# TempEnhanced.net
KiCad netlist of a schematic drawn in Altium Designer
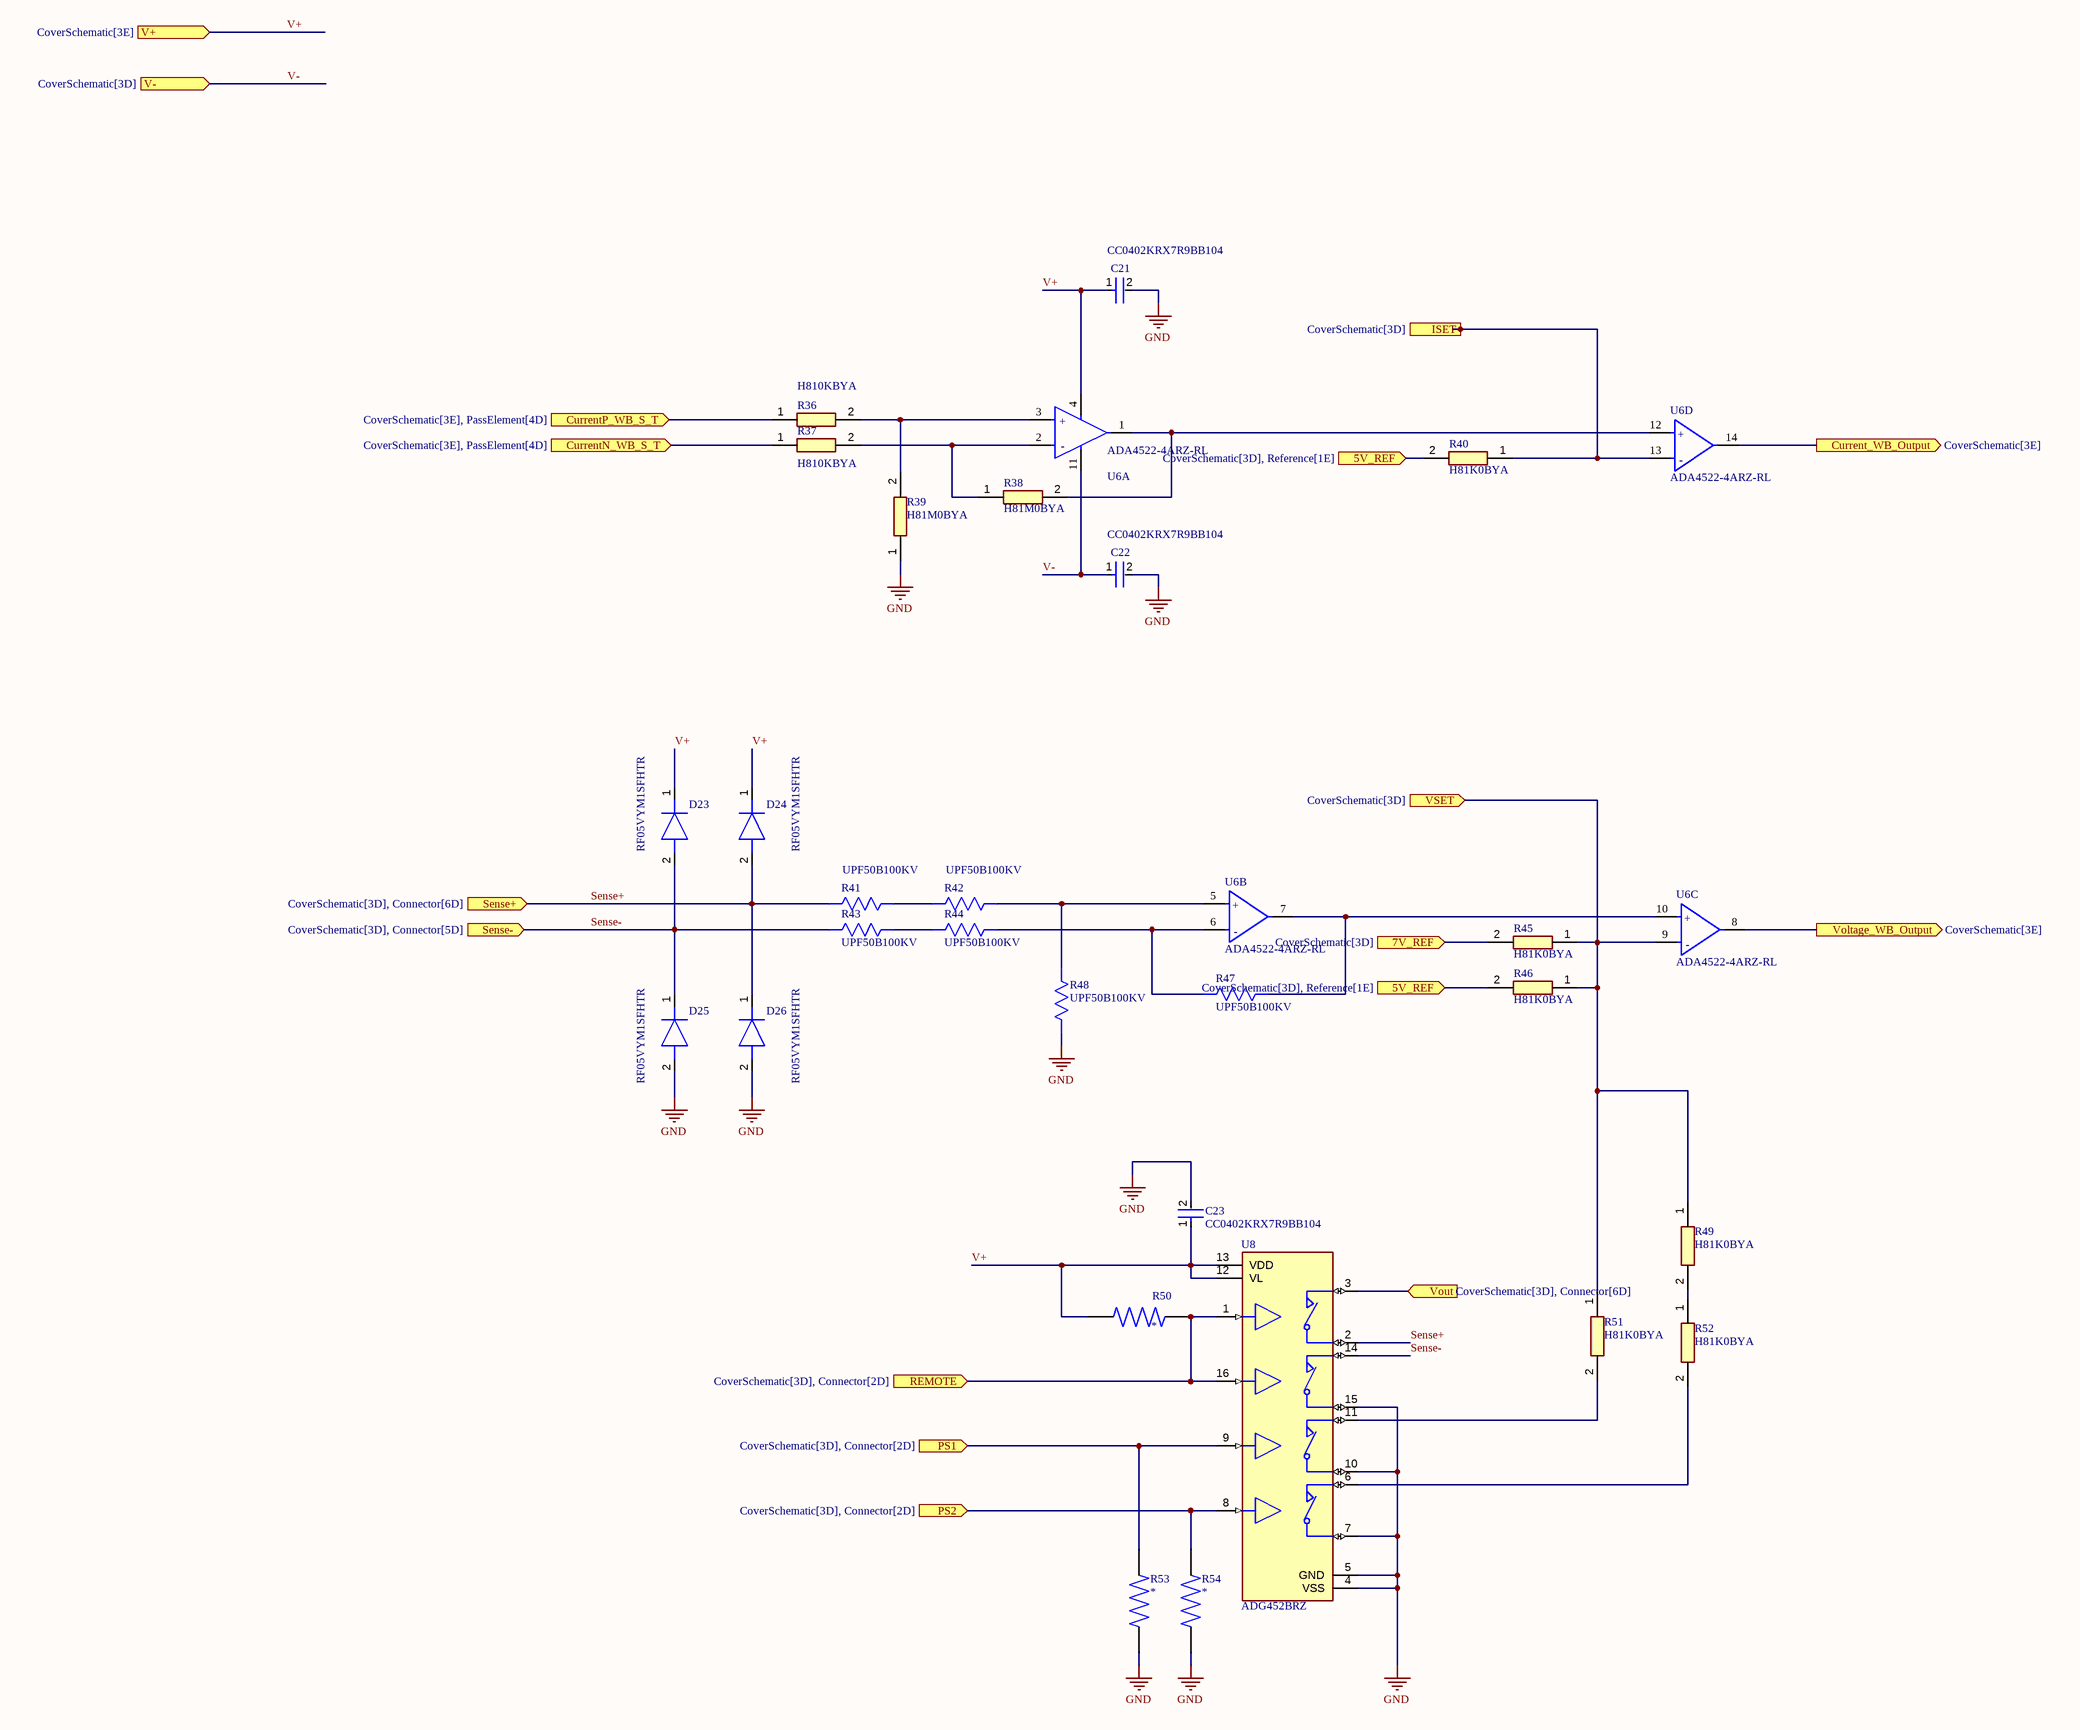
[diagram p0: TempEnhanced.SchDoc]

(export (version "E")
  (design (tool "Eeschema 10.0.6"))
  (components
    (comp (ref "C21")
      (value "CC0402KRX7R9BB104")
      (footprint "FP-CC0402-MFG")
      (description "CAP CER 0.1UF 50V X7R 0402")
      (fields
        (field (name "MANUFACTURER") "YAGEO")
        (field (name "OCTOPART") "https://octopart.com/cc0402krx7r9bb104-yageo-56536067")
      )
      (libsource (lib "Altium Content Vault") (part "11868f565c42a9108669ba33697ecf6"))
    )
    (comp (ref "C22")
      (value "CC0402KRX7R9BB104")
      (footprint "FP-CC0402-MFG")
      (description "CAP CER 0.1UF 50V X7R 0402")
      (fields
        (field (name "MANUFACTURER") "YAGEO")
        (field (name "OCTOPART") "https://octopart.com/cc0402krx7r9bb104-yageo-56536067")
      )
      (libsource (lib "Altium Content Vault") (part "11868f565c42a9108669ba33697ecf6"))
    )
    (comp (ref "C23")
      (value "CC0402KRX7R9BB104")
      (footprint "FP-CC0402-MFG")
      (description "CAP CER 0.1UF 50V X7R 0402")
      (fields
        (field (name "MANUFACTURER") "YAGEO")
        (field (name "OCTOPART") "https://octopart.com/cc0402krx7r9bb104-yageo-56536067")
      )
      (libsource (lib "Altium Content Vault") (part "11868f565c42a9108669ba33697ecf6"))
    )
    (comp (ref "D23")
      (value "RF05VYM1SFHTR")
      (footprint "SamacSys:RF05VYM1SFHTR")
      (description "Diode")
      (fields (field (name "MOUSER PART NUMBER") "755-RF05VYM1SFHTR"))
      (libsource (lib "*") (part "RF05VYM1SFHTR"))
    )
    (comp (ref "D24")
      (value "RF05VYM1SFHTR")
      (footprint "SamacSys:RF05VYM1SFHTR")
      (description "Diode")
      (fields (field (name "MOUSER PART NUMBER") "755-RF05VYM1SFHTR"))
      (libsource (lib "*") (part "RF05VYM1SFHTR"))
    )
    (comp (ref "D25")
      (value "RF05VYM1SFHTR")
      (footprint "SamacSys:RF05VYM1SFHTR")
      (description "Diode")
      (fields (field (name "MOUSER PART NUMBER") "755-RF05VYM1SFHTR"))
      (libsource (lib "*") (part "RF05VYM1SFHTR"))
    )
    (comp (ref "D26")
      (value "RF05VYM1SFHTR")
      (footprint "SamacSys:RF05VYM1SFHTR")
      (description "Diode")
      (fields (field (name "MOUSER PART NUMBER") "755-RF05VYM1SFHTR"))
      (libsource (lib "*") (part "RF05VYM1SFHTR"))
    )
    (comp (ref "R36")
      (value "H810KBYA")
      (footprint "SamacSys:RESAD1690W60L710D245")
      (description "Resistor")
      (fields (field (name "MOUSER PART NUMBER") "279-H810KBYA"))
      (libsource (lib "") (part "H810KBYA_2"))
    )
    (comp (ref "R37")
      (value "H810KBYA")
      (footprint "SamacSys:RESAD1690W60L710D245")
      (description "Resistor")
      (fields (field (name "MOUSER PART NUMBER") "279-H810KBYA"))
      (libsource (lib "") (part "H810KBYA_2"))
    )
    (comp (ref "R38")
      (value "H81M0BYA")
      (footprint "SamacSys:RESAD1690W60L710D245")
      (description "Resistor")
      (fields
        (field (name "MANUFACTURER_PART_NUMBER") "H810KBYA")
        (field (name "MOUSER PART NUMBER") "279-H810KBYA")
      )
      (libsource (lib "") (part "H810KBYA_2"))
    )
    (comp (ref "R39")
      (value "H81M0BYA")
      (footprint "SamacSys:RESAD1690W60L710D245")
      (description "Resistor")
      (fields
        (field (name "MANUFACTURER_PART_NUMBER") "H810KBYA")
        (field (name "MOUSER PART NUMBER") "279-H810KBYA")
      )
      (libsource (lib "") (part "H810KBYA_3"))
    )
    (comp (ref "R40")
      (value "H81K0BYA")
      (footprint "SamacSys:RESAD1690W60L710D245")
      (description "Resistor")
      (fields
        (field (name "MANUFACTURER_PART_NUMBER") "H810KBYA")
        (field (name "MOUSER PART NUMBER") "279-H810KBYA")
      )
      (libsource (lib "") (part "H810KBYA_1"))
    )
    (comp (ref "R41")
      (value "UPF50B100KV")
      (footprint "RES_UPF50B2K0V_TEC")
      (description "No Description Available")
      (libsource (lib "UPF50B100RV") (part "UPF50B100RV"))
    )
    (comp (ref "R42")
      (value "UPF50B100KV")
      (footprint "RES_UPF50B2K0V_TEC")
      (description "No Description Available")
      (libsource (lib "UPF50B100RV") (part "UPF50B100RV"))
    )
    (comp (ref "R43")
      (value "UPF50B100KV")
      (footprint "RES_UPF50B2K0V_TEC")
      (description "No Description Available")
      (libsource (lib "UPF50B100RV") (part "UPF50B100RV"))
    )
    (comp (ref "R44")
      (value "UPF50B100KV")
      (footprint "RES_UPF50B2K0V_TEC")
      (description "No Description Available")
      (libsource (lib "UPF50B100RV") (part "UPF50B100RV"))
    )
    (comp (ref "R45")
      (value "H81K0BYA")
      (footprint "SamacSys:RESAD1690W60L710D245")
      (description "Resistor")
      (fields
        (field (name "MANUFACTURER_PART_NUMBER") "H810KBYA")
        (field (name "MOUSER PART NUMBER") "279-H810KBYA")
      )
      (libsource (lib "") (part "H810KBYA_1"))
    )
    (comp (ref "R46")
      (value "H81K0BYA")
      (footprint "SamacSys:RESAD1690W60L710D245")
      (description "Resistor")
      (fields
        (field (name "MANUFACTURER_PART_NUMBER") "H810KBYA")
        (field (name "MOUSER PART NUMBER") "279-H810KBYA")
      )
      (libsource (lib "") (part "H810KBYA_1"))
    )
    (comp (ref "R47")
      (value "UPF50B100KV")
      (footprint "RES_UPF50B2K0V_TEC")
      (description "No Description Available")
      (libsource (lib "UPF50B100RV") (part "UPF50B100RV"))
    )
    (comp (ref "R48")
      (value "UPF50B100KV")
      (footprint "RES_UPF50B2K0V_TEC")
      (description "No Description Available")
      (libsource (lib "UPF50B100RV") (part "UPF50B100RV"))
    )
    (comp (ref "R49")
      (value "H81K0BYA")
      (footprint "SamacSys:RESAD1690W60L710D245")
      (description "Resistor")
      (fields
        (field (name "MANUFACTURER_PART_NUMBER") "H810KBYA")
        (field (name "MOUSER PART NUMBER") "279-H810KBYA")
      )
      (libsource (lib "SamacSys") (part "H810KBYA"))
    )
    (comp (ref "R50")
      (value "MCT06030C1001FP500")
      (footprint "MCT06030C1001FP500:RESC1508X55N")
      (description "Res Thin Film 0603 1K Ohm 1% 0.1W(1/10W) ?50ppm/C Molded SMD Automotive Medical T/R")
      (fields (field (name "ALTIUM_VALUE") "*") (field (name "MF") "{'manufacturer': u'Vishay Beyschlag'}"))
      (libsource (lib "MCT06030C1001FP500") (part "MCT06030C1001FP500"))
    )
    (comp (ref "R51")
      (value "H81K0BYA")
      (footprint "SamacSys:RESAD1690W60L710D245")
      (description "Resistor")
      (fields
        (field (name "MANUFACTURER_PART_NUMBER") "H810KBYA")
        (field (name "MOUSER PART NUMBER") "279-H810KBYA")
      )
      (libsource (lib "SamacSys") (part "H810KBYA"))
    )
    (comp (ref "R52")
      (value "H81K0BYA")
      (footprint "SamacSys:RESAD1690W60L710D245")
      (description "Resistor")
      (fields
        (field (name "MANUFACTURER_PART_NUMBER") "H810KBYA")
        (field (name "MOUSER PART NUMBER") "279-H810KBYA")
      )
      (libsource (lib "SamacSys") (part "H810KBYA"))
    )
    (comp (ref "R53")
      (value "MCT06030C1001FP500")
      (footprint "MCT06030C1001FP500:RESC1508X55N")
      (description "Res Thin Film 0603 1K Ohm 1% 0.1W(1/10W) ?50ppm/C Molded SMD Automotive Medical T/R")
      (fields (field (name "ALTIUM_VALUE") "*") (field (name "MF") "{'manufacturer': u'Vishay Beyschlag'}"))
      (libsource (lib "MCT06030C1001FP500") (part "MCT06030C1001FP500"))
    )
    (comp (ref "R54")
      (value "MCT06030C1001FP500")
      (footprint "MCT06030C1001FP500:RESC1508X55N")
      (description "Res Thin Film 0603 1K Ohm 1% 0.1W(1/10W) ?50ppm/C Molded SMD Automotive Medical T/R")
      (fields (field (name "ALTIUM_VALUE") "*") (field (name "MF") "{'manufacturer': u'Vishay Beyschlag'}"))
      (libsource (lib "MCT06030C1001FP500") (part "MCT06030C1001FP500"))
    )
    (comp (ref "U6")
      (value "ADA4522-4ARZ-RL")
      (footprint "FP-R-14-IPC_C")
      (description "IC OPAMP ZERO-DRIFT 4CIRC 14SOIC")
      (libsource (lib "Altium Content Vault") (part "684fa0f315d4229452f837ea2b10642"))
    )
    (comp (ref "U8")
      (value "ADG452BRZ")
      (footprint "FP-R-16-IPC_B")
      (description "IC SWITCH QUAD SPST 16SOIC")
      (fields
        (field (name "MANUFACTURER") "Analog Devices")
        (field (name "OCTOPART") "https://octopart.com/adg452brz-analog+devices-512739")
      )
      (libsource (lib "Altium Content Vault") (part "fd5cf39d1678b9618505e98b04e09e5"))
    )
  )
  (nets
    (net (code "1") (name "/5V_REF") (class "Default")
      (node (ref "R40") (pin "2") (pinfunction "2_2") (pintype "passive"))
      (node (ref "R46") (pin "2") (pinfunction "2_2") (pintype "passive"))
    )
    (net (code "2") (name "/7V_REF") (class "Default")
      (node (ref "R45") (pin "2") (pinfunction "2_2") (pintype "passive"))
    )
    (net (code "3") (name "/CurrentN_WB_S_T") (class "Default")
      (node (ref "R37") (pin "1") (pinfunction "1_1") (pintype "passive"))
    )
    (net (code "4") (name "/CurrentP_WB_S_T") (class "Default")
      (node (ref "R36") (pin "1") (pinfunction "1_1") (pintype "passive"))
    )
    (net (code "5") (name "/Current_WB_Output") (class "Default")
      (node (ref "U6") (pin "14") (pinfunction "OUT_D_14") (pintype "passive"))
    )
    (net (code "6") (name "/ISET") (class "Default")
      (node (ref "R40") (pin "1") (pinfunction "1_1") (pintype "passive"))
      (node (ref "U6") (pin "13") (pinfunction "-IN_D_13") (pintype "tri_state"))
    )
    (net (code "7") (name "/PS1") (class "Default")
      (node (ref "R53") (pin "2") (pinfunction "2_2") (pintype "passive"))
      (node (ref "U8") (pin "9") (pinfunction "IN3_9") (pintype "input"))
    )
    (net (code "8") (name "/PS2") (class "Default")
      (node (ref "R54") (pin "2") (pinfunction "2_2") (pintype "passive"))
      (node (ref "U8") (pin "8") (pinfunction "IN4_8") (pintype "input"))
    )
    (net (code "9") (name "/REMOTE") (class "Default")
      (node (ref "R50") (pin "2") (pinfunction "2_2") (pintype "passive"))
      (node (ref "U8") (pin "1") (pinfunction "IN1_1") (pintype "input"))
      (node (ref "U8") (pin "16") (pinfunction "IN2_16") (pintype "input"))
    )
    (net (code "10") (name "/Sense+") (class "Default")
      (node (ref "D24") (pin "2") (pinfunction "A_2") (pintype "passive"))
      (node (ref "D26") (pin "1") (pinfunction "K_1") (pintype "passive"))
      (node (ref "R41") (pin "2") (pinfunction "2_2") (pintype "passive"))
      (node (ref "U8") (pin "2") (pinfunction "D1_2") (pintype "bidirectional"))
    )
    (net (code "11") (name "/Sense-") (class "Default")
      (node (ref "D23") (pin "2") (pinfunction "A_2") (pintype "passive"))
      (node (ref "D25") (pin "1") (pinfunction "K_1") (pintype "passive"))
      (node (ref "R43") (pin "2") (pinfunction "2_2") (pintype "passive"))
      (node (ref "U8") (pin "14") (pinfunction "S2_14") (pintype "bidirectional"))
    )
    (net (code "12") (name "/V+") (class "Default")
      (node (ref "C21") (pin "1") (pinfunction "1_1") (pintype "passive"))
      (node (ref "C23") (pin "1") (pinfunction "1_1") (pintype "passive"))
      (node (ref "D23") (pin "1") (pinfunction "K_1") (pintype "passive"))
      (node (ref "D24") (pin "1") (pinfunction "K_1") (pintype "passive"))
      (node (ref "R50") (pin "1") (pinfunction "1_1") (pintype "passive"))
      (node (ref "U6") (pin "4") (pinfunction "V+_4") (pintype "power_in"))
      (node (ref "U8") (pin "12") (pinfunction "VL_12") (pintype "power_in"))
      (node (ref "U8") (pin "13") (pinfunction "VDD_13") (pintype "power_in"))
    )
    (net (code "13") (name "/V-") (class "Default")
      (node (ref "C22") (pin "1") (pinfunction "1_1") (pintype "passive"))
      (node (ref "U6") (pin "11") (pinfunction "V-_11") (pintype "power_in"))
    )
    (net (code "14") (name "/VSET") (class "Default")
      (node (ref "R45") (pin "1") (pinfunction "1_1") (pintype "passive"))
      (node (ref "R46") (pin "1") (pinfunction "1_1") (pintype "passive"))
      (node (ref "R49") (pin "1") (pinfunction "1_1") (pintype "passive"))
      (node (ref "R51") (pin "1") (pinfunction "1_1") (pintype "passive"))
      (node (ref "U6") (pin "9") (pinfunction "-IN_C_9") (pintype "tri_state"))
    )
    (net (code "15") (name "/Voltage_WB_Output") (class "Default")
      (node (ref "U6") (pin "8") (pinfunction "OUT_C_8") (pintype "passive"))
    )
    (net (code "16") (name "/Vout") (class "Default")
      (node (ref "U8") (pin "3") (pinfunction "S1_3") (pintype "bidirectional"))
    )
    (net (code "17") (name "GND") (class "Default")
      (node (ref "C21") (pin "2") (pinfunction "2_2") (pintype "passive"))
      (node (ref "C22") (pin "2") (pinfunction "2_2") (pintype "passive"))
      (node (ref "C23") (pin "2") (pinfunction "2_2") (pintype "passive"))
      (node (ref "D25") (pin "2") (pinfunction "A_2") (pintype "passive"))
      (node (ref "D26") (pin "2") (pinfunction "A_2") (pintype "passive"))
      (node (ref "R39") (pin "1") (pinfunction "1_1") (pintype "passive"))
      (node (ref "R48") (pin "2") (pinfunction "2_2") (pintype "passive"))
      (node (ref "R53") (pin "1") (pinfunction "1_1") (pintype "passive"))
      (node (ref "R54") (pin "1") (pinfunction "1_1") (pintype "passive"))
      (node (ref "U8") (pin "10") (pinfunction "D3_10") (pintype "bidirectional"))
      (node (ref "U8") (pin "15") (pinfunction "D2_15") (pintype "bidirectional"))
      (node (ref "U8") (pin "4") (pinfunction "VSS_4") (pintype "power_in"))
      (node (ref "U8") (pin "5") (pinfunction "GND_5") (pintype "power_in"))
      (node (ref "U8") (pin "7") (pinfunction "D4_7") (pintype "bidirectional"))
    )
    (net (code "18") (name "Net-(R41-Pad1)") (class "Default")
      (node (ref "R41") (pin "1") (pinfunction "1_1") (pintype "passive"))
      (node (ref "R42") (pin "2") (pinfunction "2_2") (pintype "passive"))
    )
    (net (code "19") (name "Net-(R43-Pad1)") (class "Default")
      (node (ref "R43") (pin "1") (pinfunction "1_1") (pintype "passive"))
      (node (ref "R44") (pin "2") (pinfunction "2_2") (pintype "passive"))
    )
    (net (code "20") (name "Net-(R49-Pad2)") (class "Default")
      (node (ref "R49") (pin "2") (pinfunction "2_2") (pintype "passive"))
      (node (ref "R52") (pin "1") (pinfunction "1_1") (pintype "passive"))
    )
    (net (code "21") (name "Net-(U6A-+IN_A)") (class "Default")
      (node (ref "R36") (pin "2") (pinfunction "2_2") (pintype "passive"))
      (node (ref "R39") (pin "2") (pinfunction "2_2") (pintype "passive"))
      (node (ref "U6") (pin "3") (pinfunction "+IN_A_3") (pintype "tri_state"))
    )
    (net (code "22") (name "Net-(U6A--IN_A)") (class "Default")
      (node (ref "R37") (pin "2") (pinfunction "2_2") (pintype "passive"))
      (node (ref "R38") (pin "1") (pinfunction "1_1") (pintype "passive"))
      (node (ref "U6") (pin "2") (pinfunction "-IN_A_2") (pintype "tri_state"))
    )
    (net (code "23") (name "Net-(U6A-OUT_A)") (class "Default")
      (node (ref "R38") (pin "2") (pinfunction "2_2") (pintype "passive"))
      (node (ref "U6") (pin "1") (pinfunction "OUT_A_1") (pintype "passive"))
      (node (ref "U6") (pin "12") (pinfunction "+IN_D_12") (pintype "tri_state"))
    )
    (net (code "24") (name "Net-(U6B-+IN_B)") (class "Default")
      (node (ref "R42") (pin "1") (pinfunction "1_1") (pintype "passive"))
      (node (ref "R48") (pin "1") (pinfunction "1_1") (pintype "passive"))
      (node (ref "U6") (pin "5") (pinfunction "+IN_B_5") (pintype "tri_state"))
    )
    (net (code "25") (name "Net-(U6B--IN_B)") (class "Default")
      (node (ref "R44") (pin "1") (pinfunction "1_1") (pintype "passive"))
      (node (ref "R47") (pin "2") (pinfunction "2_2") (pintype "passive"))
      (node (ref "U6") (pin "6") (pinfunction "-IN_B_6") (pintype "tri_state"))
    )
    (net (code "26") (name "Net-(U6B-OUT_B)") (class "Default")
      (node (ref "R47") (pin "1") (pinfunction "1_1") (pintype "passive"))
      (node (ref "U6") (pin "10") (pinfunction "+IN_C_10") (pintype "tri_state"))
      (node (ref "U6") (pin "7") (pinfunction "OUT_B_7") (pintype "passive"))
    )
    (net (code "27") (name "Net-(U8-S3)") (class "Default")
      (node (ref "R51") (pin "2") (pinfunction "2_2") (pintype "passive"))
      (node (ref "U8") (pin "11") (pinfunction "S3_11") (pintype "bidirectional"))
    )
    (net (code "28") (name "Net-(U8-S4)") (class "Default")
      (node (ref "R52") (pin "2") (pinfunction "2_2") (pintype "passive"))
      (node (ref "U8") (pin "6") (pinfunction "S4_6") (pintype "bidirectional"))
    )
  )
)
